# MCU025B_AltRouting_Misc.net
KiCad netlist of a schematic drawn in Altium Designer
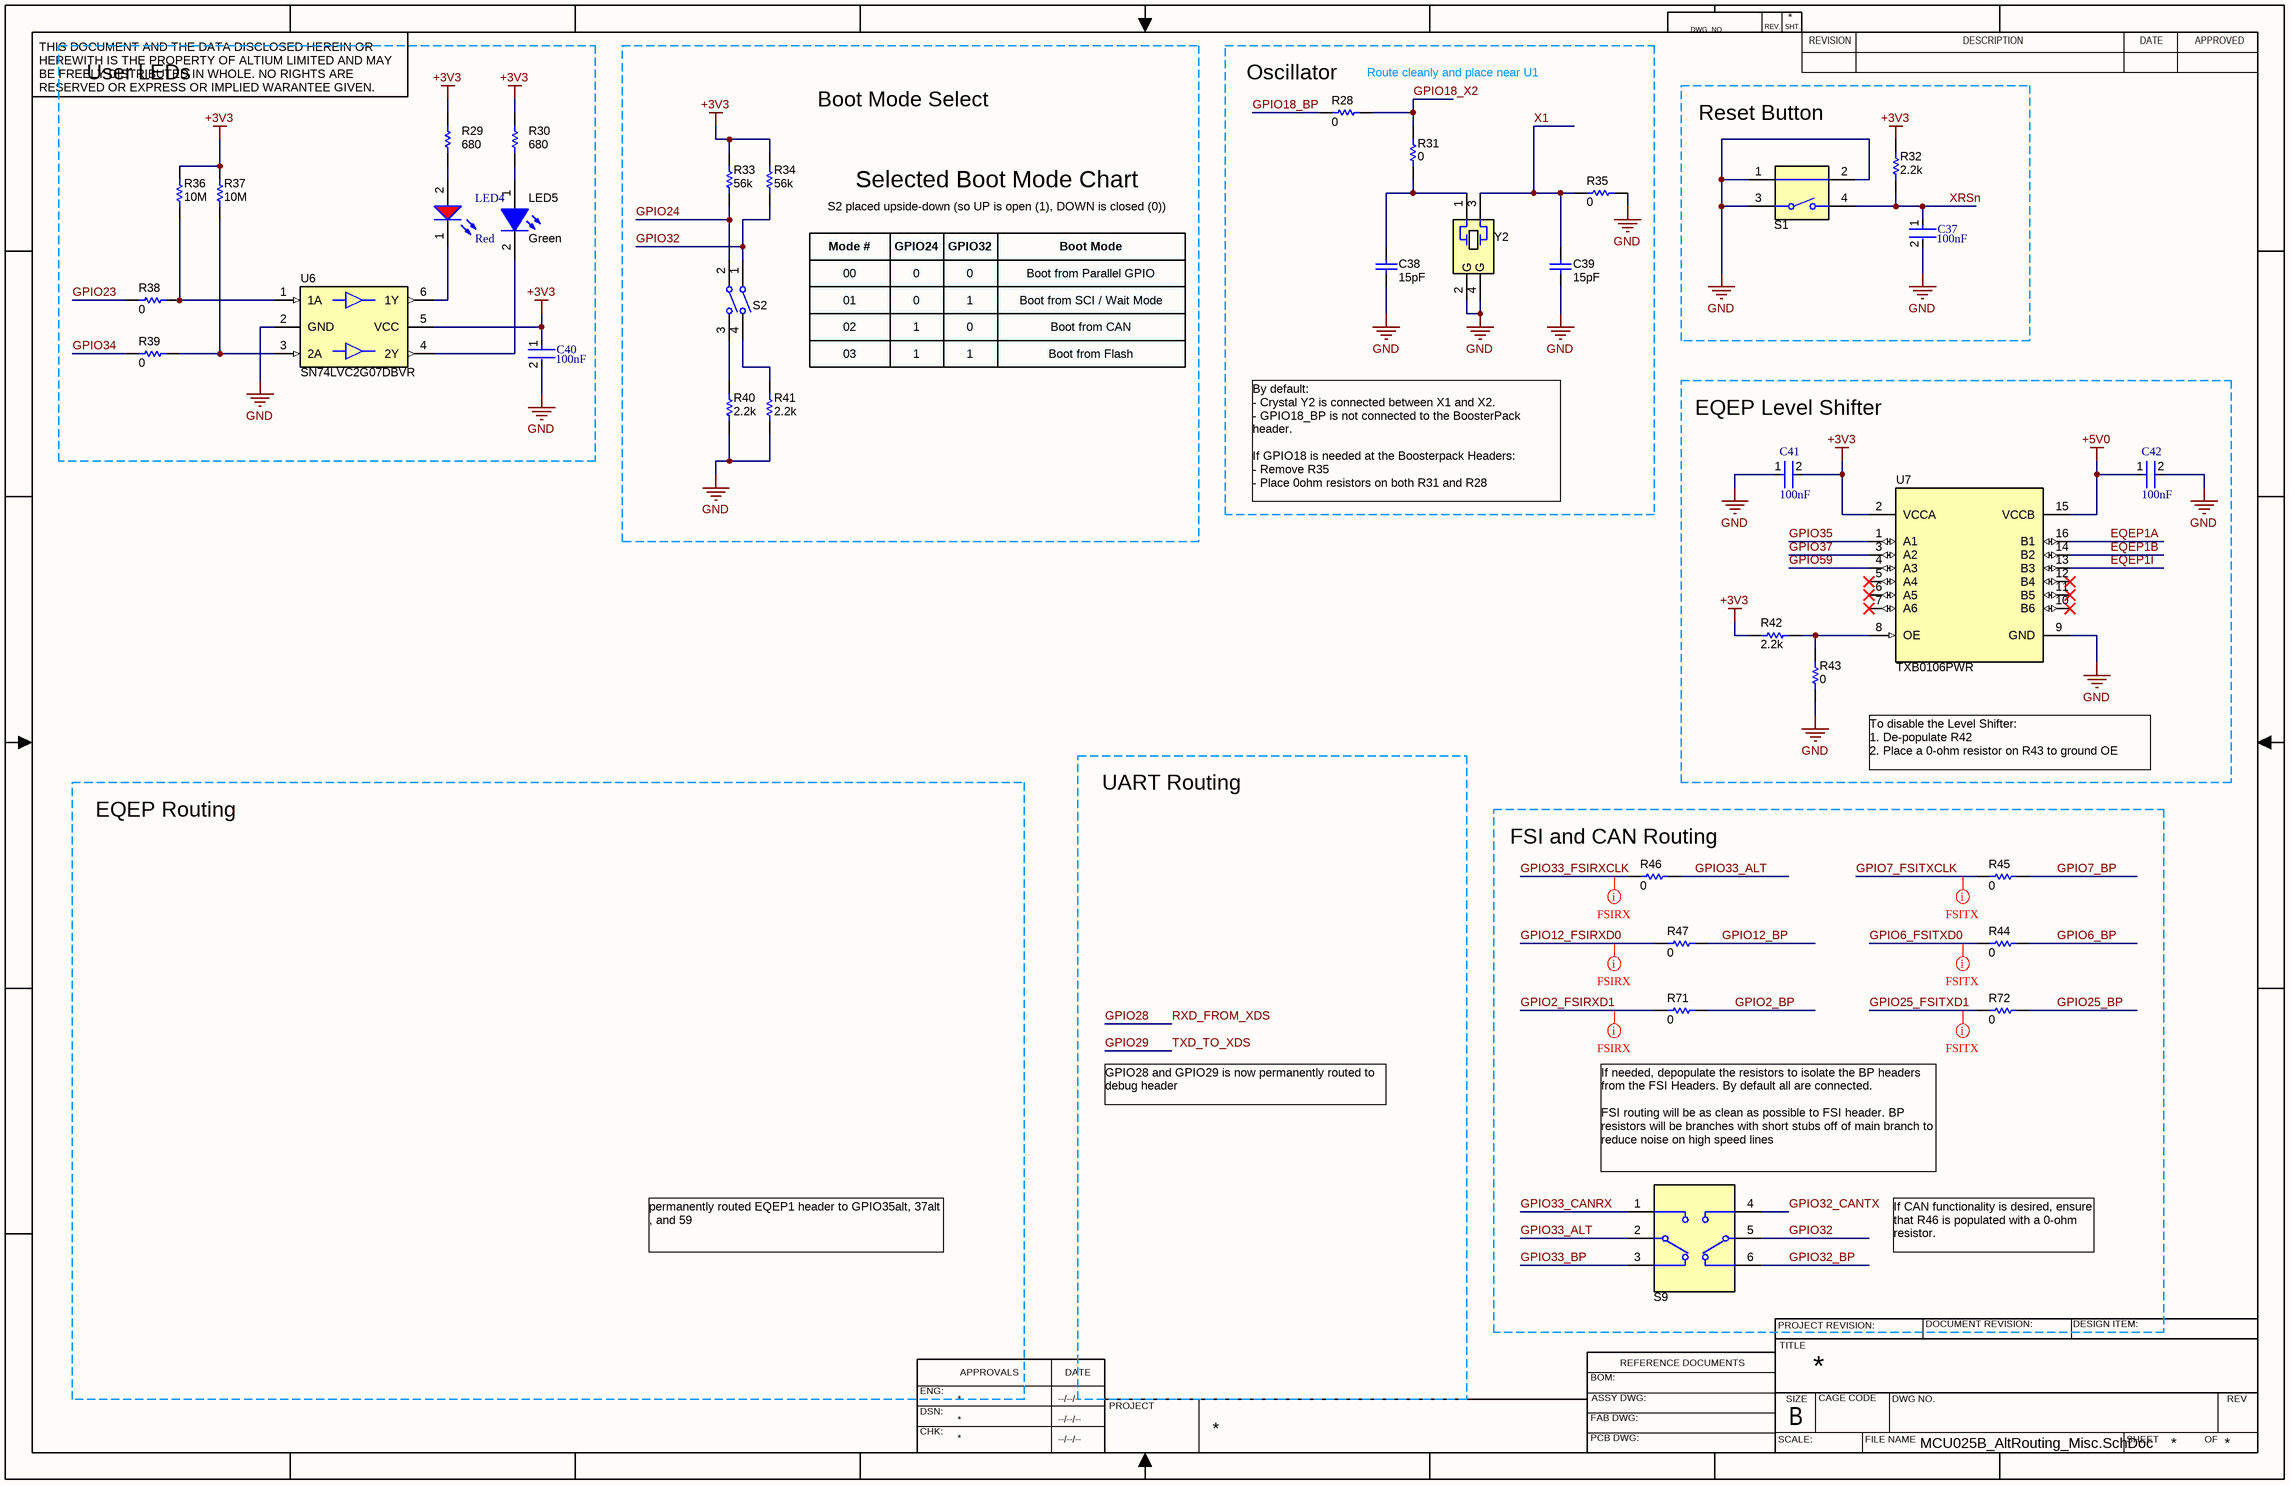
[diagram p0: MCU025B_AltRouting_Misc.SchDoc]

(export (version "E")
  (design (tool "Eeschema 10.0.6"))
  (components
    (comp (ref "C37")
      (value "CL10B104KA8NFNC")
      (footprint "FP-CL10-IPC_C")
      (description "Cap Ceramic 100nF 25V X7R ±10% Pad SMD 0603 +125°C T/R")
      (fields (field (name "TOLERANCE") "10%") (field (name "CAPACITANCE") "100nF"))
      (libsource (lib "Altium Content Vault") (part "b4654b650e69147ec39a6b967a45e02"))
    )
    (comp (ref "C38")
      (value "GRM1555C1H150JA01D")
      (footprint "0402")
      (description "CAP, CERM, 15 pF, 50 V, +/- 5%, C0G/NP0, 0402")
      (fields
        (field (name "VALUEDISPLAYED") "15pF")
        (field (name "MANUFACTURER") "MuRata")
        (field (name "PUBLISHER") "Texas Instruments")
      )
      (libsource (lib "Altium Vault - TI") (part "Capacitor"))
    )
    (comp (ref "C39")
      (value "GRM1555C1H150JA01D")
      (footprint "0402")
      (description "CAP, CERM, 15 pF, 50 V, +/- 5%, C0G/NP0, 0402")
      (fields
        (field (name "VALUEDISPLAYED") "15pF")
        (field (name "MANUFACTURER") "MuRata")
        (field (name "PUBLISHER") "Texas Instruments")
      )
      (libsource (lib "Altium Vault - TI") (part "Capacitor"))
    )
    (comp (ref "C40")
      (value "CL10B104KA8NFNC")
      (footprint "FP-CL10-IPC_C")
      (description "Cap Ceramic 100nF 25V X7R ±10% Pad SMD 0603 +125°C T/R")
      (fields (field (name "TOLERANCE") "10%") (field (name "CAPACITANCE") "100nF"))
      (libsource (lib "Altium Content Vault") (part "b4654b650e69147ec39a6b967a45e02"))
    )
    (comp (ref "C41")
      (value "CL10B104KA8NFNC")
      (footprint "FP-CL10-IPC_C")
      (description "Cap Ceramic 100nF 25V X7R ±10% Pad SMD 0603 +125°C T/R")
      (fields (field (name "TOLERANCE") "10%") (field (name "CAPACITANCE") "100nF"))
      (libsource (lib "Altium Content Vault") (part "b4654b650e69147ec39a6b967a45e02"))
    )
    (comp (ref "C42")
      (value "CL10B104KA8NFNC")
      (footprint "FP-CL10-IPC_C")
      (description "Cap Ceramic 100nF 25V X7R ±10% Pad SMD 0603 +125°C T/R")
      (fields (field (name "TOLERANCE") "10%") (field (name "CAPACITANCE") "100nF"))
      (libsource (lib "Altium Content Vault") (part "b4654b650e69147ec39a6b967a45e02"))
    )
    (comp (ref "LED4")
      (value "150080SS75000")
      (footprint "WL-SMCW_0805_150080xx75000")
      (description "Led, Red, 630 Nm, 1.9 V, 30 Ma, 60 Mcd Rohs Compliant: Yes")
      (fields (field (name "COLOR") "Red"))
      (libsource (lib "Altium Content Vault") (part "LED_Red_2A-1K"))
    )
    (comp (ref "LED5")
      (value "Green")
      (footprint "LED_LTST-C171")
      (description "LED, Green, SMD")
      (fields
        (field (name "MANUFACTURER") "Lite-On")
        (field (name "PARTNUMBER") "LTST-C171GKT")
        (field (name "PUBLISHER") "Texas Instruments")
      )
      (libsource (lib "Altium Vault - TI") (part "LED"))
    )
    (comp (ref "R28")
      (value "CRCW06030000Z0EA")
      (footprint "0603")
      (description "RES, 0, 5%, 0.1 W, AEC-Q200 Grade 0, 0603")
      (fields (field (name "VALUEDISPLAYED") "0") (field (name "MANUFACTURER") "Vishay-Dale"))
      (libsource (lib "Altium Vault - TI") (part "Resistor"))
    )
    (comp (ref "R29")
      (value "CRCW0402680RJNED")
      (footprint "0402")
      (description "RES, 680, 5%, 0.063 W, AEC-Q200 Grade 0, 0402")
      (fields (field (name "MANUFACTURER") "Vishay-Dale") (field (name "VALUEDISPLAYED") "680"))
      (libsource (lib "Altium Vault - TI") (part "CMP-0026962-3"))
    )
    (comp (ref "R30")
      (value "CRCW0402680RJNED")
      (footprint "0402")
      (description "RES, 680, 5%, 0.063 W, AEC-Q200 Grade 0, 0402")
      (fields (field (name "MANUFACTURER") "Vishay-Dale") (field (name "VALUEDISPLAYED") "680"))
      (libsource (lib "Altium Vault - TI") (part "CMP-0026962-3"))
    )
    (comp (ref "R31")
      (value "CRCW06030000Z0EA")
      (footprint "0603")
      (description "RES, 0, 5%, 0.1 W, AEC-Q200 Grade 0, 0603")
      (fields (field (name "VALUEDISPLAYED") "0") (field (name "MANUFACTURER") "Vishay-Dale"))
      (libsource (lib "Altium Vault - TI") (part "Resistor"))
    )
    (comp (ref "R32")
      (value "CRCW04022K20JNED")
      (footprint "0402")
      (description "RES, 2.2 k, 5%, 0.063 W, AEC-Q200 Grade 0, 0402")
      (fields (field (name "VALUEDISPLAYED") "2.2k") (field (name "MANUFACTURER") "Vishay-Dale"))
      (libsource (lib "Altium Vault - TI") (part "Resistor"))
    )
    (comp (ref "R33")
      (value "CRCW040256K0JNED")
      (footprint "0402")
      (description "RES, 56 k, 5%, 0.063 W, AEC-Q200 Grade 0, 0402")
      (fields (field (name "VALUEDISPLAYED") "56k") (field (name "MANUFACTURER") "Vishay-Dale"))
      (libsource (lib "Altium Vault - TI") (part "Resistor"))
    )
    (comp (ref "R34")
      (value "CRCW040256K0JNED")
      (footprint "0402")
      (description "RES, 56 k, 5%, 0.063 W, AEC-Q200 Grade 0, 0402")
      (fields (field (name "VALUEDISPLAYED") "56k") (field (name "MANUFACTURER") "Vishay-Dale"))
      (libsource (lib "Altium Vault - TI") (part "Resistor"))
    )
    (comp (ref "R35")
      (value "CRCW06030000Z0EA")
      (footprint "0603")
      (description "RES, 0, 5%, 0.1 W, AEC-Q200 Grade 0, 0603")
      (fields (field (name "VALUEDISPLAYED") "0") (field (name "MANUFACTURER") "Vishay-Dale"))
      (libsource (lib "Altium Vault - TI") (part "Resistor"))
    )
    (comp (ref "R36")
      (value "CRCW040210M0JNED")
      (footprint "0402")
      (description "RES, 10 M, 5%, 0.063 W, AEC-Q200 Grade 0, 0402")
      (fields (field (name "VALUEDISPLAYED") "10M") (field (name "MANUFACTURER") "Vishay-Dale"))
      (libsource (lib "Altium Vault - TI") (part "Resistor"))
    )
    (comp (ref "R37")
      (value "CRCW040210M0JNED")
      (footprint "0402")
      (description "RES, 10 M, 5%, 0.063 W, AEC-Q200 Grade 0, 0402")
      (fields (field (name "VALUEDISPLAYED") "10M") (field (name "MANUFACTURER") "Vishay-Dale"))
      (libsource (lib "Altium Vault - TI") (part "Resistor"))
    )
    (comp (ref "R38")
      (value "CRCW06030000Z0EA")
      (footprint "0603")
      (description "RES, 0, 5%, 0.1 W, AEC-Q200 Grade 0, 0603")
      (fields (field (name "VALUEDISPLAYED") "0") (field (name "MANUFACTURER") "Vishay-Dale"))
      (libsource (lib "Altium Vault - TI") (part "Resistor"))
    )
    (comp (ref "R39")
      (value "CRCW06030000Z0EA")
      (footprint "0603")
      (description "RES, 0, 5%, 0.1 W, AEC-Q200 Grade 0, 0603")
      (fields (field (name "VALUEDISPLAYED") "0") (field (name "MANUFACTURER") "Vishay-Dale"))
      (libsource (lib "Altium Vault - TI") (part "Resistor"))
    )
    (comp (ref "R40")
      (value "CRCW04022K20JNED")
      (footprint "0402")
      (description "RES, 2.2 k, 5%, 0.063 W, AEC-Q200 Grade 0, 0402")
      (fields (field (name "VALUEDISPLAYED") "2.2k") (field (name "MANUFACTURER") "Vishay-Dale"))
      (libsource (lib "Altium Vault - TI") (part "Resistor"))
    )
    (comp (ref "R41")
      (value "CRCW04022K20JNED")
      (footprint "0402")
      (description "RES, 2.2 k, 5%, 0.063 W, AEC-Q200 Grade 0, 0402")
      (fields (field (name "VALUEDISPLAYED") "2.2k") (field (name "MANUFACTURER") "Vishay-Dale"))
      (libsource (lib "Altium Vault - TI") (part "Resistor"))
    )
    (comp (ref "R42")
      (value "CRCW06032K20JNEA")
      (footprint "0603")
      (description "RES, 2.2 k, 5%, 0.1 W, AEC-Q200 Grade 0, 0603")
      (fields (field (name "VALUEDISPLAYED") "2.2k") (field (name "MANUFACTURER") "Vishay-Dale"))
      (libsource (lib "Altium Vault - TI") (part "Resistor"))
    )
    (comp (ref "R43")
      (value "CRCW06030000Z0EA")
      (footprint "0603")
      (description "RES, 0, 5%, 0.1 W, AEC-Q200 Grade 0, 0603")
      (fields (field (name "VALUEDISPLAYED") "0") (field (name "MANUFACTURER") "Vishay-Dale"))
      (libsource (lib "Altium Vault - TI") (part "Resistor"))
    )
    (comp (ref "R44")
      (value "CRCW06030000Z0EA")
      (footprint "0603")
      (description "RES, 0, 5%, 0.1 W, AEC-Q200 Grade 0, 0603")
      (fields (field (name "VALUEDISPLAYED") "0") (field (name "MANUFACTURER") "Vishay-Dale"))
      (libsource (lib "Altium Vault - TI") (part "Resistor"))
    )
    (comp (ref "R45")
      (value "CRCW06030000Z0EA")
      (footprint "0603")
      (description "RES, 0, 5%, 0.1 W, AEC-Q200 Grade 0, 0603")
      (fields (field (name "VALUEDISPLAYED") "0") (field (name "MANUFACTURER") "Vishay-Dale"))
      (libsource (lib "Altium Vault - TI") (part "Resistor"))
    )
    (comp (ref "R46")
      (value "CRCW06030000Z0EA")
      (footprint "0603")
      (description "RES, 0, 5%, 0.1 W, AEC-Q200 Grade 0, 0603")
      (fields (field (name "VALUEDISPLAYED") "0") (field (name "MANUFACTURER") "Vishay-Dale"))
      (libsource (lib "Altium Vault - TI") (part "Resistor"))
    )
    (comp (ref "R47")
      (value "CRCW06030000Z0EA")
      (footprint "0603")
      (description "RES, 0, 5%, 0.1 W, AEC-Q200 Grade 0, 0603")
      (fields (field (name "VALUEDISPLAYED") "0") (field (name "MANUFACTURER") "Vishay-Dale"))
      (libsource (lib "Altium Vault - TI") (part "Resistor"))
    )
    (comp (ref "R71")
      (value "CRCW06030000Z0EA")
      (footprint "0603")
      (description "RES, 0, 5%, 0.1 W, AEC-Q200 Grade 0, 0603")
      (fields (field (name "VALUEDISPLAYED") "0") (field (name "MANUFACTURER") "Vishay-Dale"))
      (libsource (lib "Altium Vault - TI") (part "Resistor"))
    )
    (comp (ref "R72")
      (value "CRCW06030000Z0EA")
      (footprint "0603")
      (description "RES, 0, 5%, 0.1 W, AEC-Q200 Grade 0, 0603")
      (fields (field (name "VALUEDISPLAYED") "0") (field (name "MANUFACTURER") "Vishay-Dale"))
      (libsource (lib "Altium Vault - TI") (part "Resistor"))
    )
    (comp (ref "S1")
      (value "1188E-1K2-V-TR")
      (footprint "SW_1188E")
      (description "Switch, SPST, 0.05 A, 12 VDC, SMD")
      (fields (field (name "MANUFACTURER") "Diptronics") (field (name "PUBLISHER") "Texas Instruments"))
      (libsource (lib "Altium Vault - TI") (part "SW_1188E"))
    )
    (comp (ref "S2")
      (value "218-2LPST")
      (footprint "SW_218-2LP")
      (description "Switch, SPST, 2 Pos, 25mA, 24VDC, SMD")
      (fields
        (field (name "MANUFACTURER") "CTS Electrocomponents")
        (field (name "PUBLISHER") "Texas Instruments")
      )
      (libsource (lib "Altium Vault - TI") (part "SW_2SPST"))
    )
    (comp (ref "S9")
      (value "CAS-220TA")
      (footprint "SW_CAS-220TA")
      (description "SLIDE SWITCH DPDT  .1A, SMT")
      (fields
        (field (name "MANUFACTURER") "Copal Electronics")
        (field (name "PUBLISHER") "Texas Instruments")
      )
      (libsource (lib "Altium Vault - TI") (part "SW_CAS-220TA"))
    )
    (comp (ref "U6")
      (value "SN74LVC2G07DBVR")
      (footprint "DBV0006A_N")
      (description "Dual Buffer/Driver with Open-Drain Output, DBV0006A, LARGE T&R")
      (fields
        (field (name "GENERIC PART NUMBER") "SN74LVC2G07")
        (field (name "MANUFACTURER") "Texas Instruments")
      )
      (libsource (lib "Altium Vault - TI") (part "CMP-0051789-2"))
    )
    (comp (ref "U7")
      (value "TXB0106PWR")
      (footprint "PW0016A_N")
      (fields
        (field (name "MANUFACTURER") "Texas Instruments")
        (field (name "PUBLISHER") "Texas Instruments")
      )
      (libsource (lib "Altium Vault - TI") (part "TXB0106PW"))
    )
    (comp (ref "Y2")
      (value "ECS-200-18-30B-AGN-TR")
      (footprint "ECS_ECX-53B")
      (description "Crystal, 20 MHz, 25 ppm, 18, SMD")
      (fields (field (name "MANUFACTURER") "ECS Inc."))
      (libsource (lib "Altium Vault - TI") (part "CMP-0080365-1"))
    )
  )
  (nets
    (net (code "1") (name "+3V3") (class "Default")
      (node (ref "C40") (pin "1") (pinfunction "1_1") (pintype "passive"))
      (node (ref "C41") (pin "2") (pinfunction "2_2") (pintype "passive"))
      (node (ref "R29") (pin "2") (pinfunction "2_2") (pintype "passive"))
      (node (ref "R30") (pin "2") (pinfunction "2_2") (pintype "passive"))
      (node (ref "R32") (pin "2") (pinfunction "2_2") (pintype "passive"))
      (node (ref "R33") (pin "2") (pinfunction "2_2") (pintype "passive"))
      (node (ref "R34") (pin "2") (pinfunction "2_2") (pintype "passive"))
      (node (ref "R36") (pin "2") (pinfunction "2_2") (pintype "passive"))
      (node (ref "R37") (pin "2") (pinfunction "2_2") (pintype "passive"))
      (node (ref "R42") (pin "1") (pinfunction "1_1") (pintype "passive"))
      (node (ref "U6") (pin "5") (pinfunction "VCC_5") (pintype "power_in"))
      (node (ref "U7") (pin "2") (pinfunction "VCCA_2") (pintype "power_in"))
    )
    (net (code "2") (name "+5V0") (class "Default")
      (node (ref "C42") (pin "1") (pinfunction "1_1") (pintype "passive"))
      (node (ref "U7") (pin "15") (pinfunction "VCCB_15") (pintype "power_in"))
    )
    (net (code "3") (name "/EQEP1A") (class "Default")
      (node (ref "U7") (pin "16") (pinfunction "B1_16") (pintype "bidirectional"))
    )
    (net (code "4") (name "/EQEP1B") (class "Default")
      (node (ref "U7") (pin "14") (pinfunction "B2_14") (pintype "bidirectional"))
    )
    (net (code "5") (name "/EQEP1I") (class "Default")
      (node (ref "U7") (pin "13") (pinfunction "B3_13") (pintype "bidirectional"))
    )
    (net (code "6") (name "/GPIO2_BP") (class "Default")
      (node (ref "R71") (pin "2") (pinfunction "2_2") (pintype "passive"))
    )
    (net (code "7") (name "/GPIO2_FSIRXD1") (class "Default")
      (node (ref "R71") (pin "1") (pinfunction "1_1") (pintype "passive"))
    )
    (net (code "8") (name "/GPIO6_BP") (class "Default")
      (node (ref "R44") (pin "2") (pinfunction "2_2") (pintype "passive"))
    )
    (net (code "9") (name "/GPIO6_FSITXD0") (class "Default")
      (node (ref "R44") (pin "1") (pinfunction "1_1") (pintype "passive"))
    )
    (net (code "10") (name "/GPIO7_BP") (class "Default")
      (node (ref "R45") (pin "2") (pinfunction "2_2") (pintype "passive"))
    )
    (net (code "11") (name "/GPIO7_FSITXCLK") (class "Default")
      (node (ref "R45") (pin "1") (pinfunction "1_1") (pintype "passive"))
    )
    (net (code "12") (name "/GPIO12_BP") (class "Default")
      (node (ref "R47") (pin "2") (pinfunction "2_2") (pintype "passive"))
    )
    (net (code "13") (name "/GPIO12_FSIRXD0") (class "Default")
      (node (ref "R47") (pin "1") (pinfunction "1_1") (pintype "passive"))
    )
    (net (code "14") (name "/GPIO18_BP") (class "Default")
      (node (ref "R28") (pin "1") (pinfunction "1_1") (pintype "passive"))
    )
    (net (code "15") (name "/GPIO18_X2") (class "Default")
      (node (ref "R28") (pin "2") (pinfunction "2_2") (pintype "passive"))
      (node (ref "R31") (pin "2") (pinfunction "2_2") (pintype "passive"))
    )
    (net (code "16") (name "/GPIO23") (class "Default")
      (node (ref "R38") (pin "1") (pinfunction "1_1") (pintype "passive"))
    )
    (net (code "17") (name "/GPIO24") (class "Default")
      (node (ref "R33") (pin "1") (pinfunction "1_1") (pintype "passive"))
      (node (ref "S2") (pin "2") (pinfunction "2_2") (pintype "passive"))
    )
    (net (code "18") (name "/GPIO25_BP") (class "Default")
      (node (ref "R72") (pin "2") (pinfunction "2_2") (pintype "passive"))
    )
    (net (code "19") (name "/GPIO25_FSITXD1") (class "Default")
      (node (ref "R72") (pin "1") (pinfunction "1_1") (pintype "passive"))
    )
    (net (code "22") (name "/GPIO32") (class "Default")
      (node (ref "R34") (pin "1") (pinfunction "1_1") (pintype "passive"))
      (node (ref "S2") (pin "1") (pinfunction "1_1") (pintype "passive"))
      (node (ref "S9") (pin "5") (pinfunction "5_5") (pintype "passive"))
    )
    (net (code "23") (name "/GPIO32_BP") (class "Default")
      (node (ref "S9") (pin "6") (pinfunction "6_6") (pintype "passive"))
    )
    (net (code "24") (name "/GPIO32_CANTX") (class "Default")
      (node (ref "S9") (pin "4") (pinfunction "4_4") (pintype "passive"))
    )
    (net (code "25") (name "/GPIO33_ALT") (class "Default")
      (node (ref "R46") (pin "2") (pinfunction "2_2") (pintype "passive"))
      (node (ref "S9") (pin "2") (pinfunction "2_2") (pintype "passive"))
    )
    (net (code "26") (name "/GPIO33_BP") (class "Default")
      (node (ref "S9") (pin "3") (pinfunction "3_3") (pintype "passive"))
    )
    (net (code "27") (name "/GPIO33_CANRX") (class "Default")
      (node (ref "S9") (pin "1") (pinfunction "1_1") (pintype "passive"))
    )
    (net (code "28") (name "/GPIO33_FSIRXCLK") (class "Default")
      (node (ref "R46") (pin "1") (pinfunction "1_1") (pintype "passive"))
    )
    (net (code "29") (name "/GPIO34") (class "Default")
      (node (ref "R39") (pin "1") (pinfunction "1_1") (pintype "passive"))
    )
    (net (code "30") (name "/GPIO35") (class "Default")
      (node (ref "U7") (pin "1") (pinfunction "A1_1") (pintype "bidirectional"))
    )
    (net (code "31") (name "/GPIO37") (class "Default")
      (node (ref "U7") (pin "3") (pinfunction "A2_3") (pintype "bidirectional"))
    )
    (net (code "32") (name "/GPIO59") (class "Default")
      (node (ref "U7") (pin "4") (pinfunction "A3_4") (pintype "bidirectional"))
    )
    (net (code "33") (name "/X1") (class "Default")
      (node (ref "C39") (pin "1") (pinfunction "1_1") (pintype "passive"))
      (node (ref "R35") (pin "1") (pinfunction "1_1") (pintype "passive"))
      (node (ref "Y2") (pin "3") (pinfunction "3_3") (pintype "passive"))
    )
    (net (code "34") (name "/XRSn") (class "Default")
      (node (ref "C37") (pin "1") (pinfunction "1_1") (pintype "passive"))
      (node (ref "R32") (pin "1") (pinfunction "1_1") (pintype "passive"))
      (node (ref "S1") (pin "4") (pinfunction "4_4") (pintype "passive"))
    )
    (net (code "35") (name "GND") (class "Default")
      (node (ref "C37") (pin "2") (pinfunction "2_2") (pintype "passive"))
      (node (ref "C38") (pin "2") (pinfunction "2_2") (pintype "passive"))
      (node (ref "C39") (pin "2") (pinfunction "2_2") (pintype "passive"))
      (node (ref "C40") (pin "2") (pinfunction "2_2") (pintype "passive"))
      (node (ref "C41") (pin "1") (pinfunction "1_1") (pintype "passive"))
      (node (ref "C42") (pin "2") (pinfunction "2_2") (pintype "passive"))
      (node (ref "R35") (pin "2") (pinfunction "2_2") (pintype "passive"))
      (node (ref "R40") (pin "1") (pinfunction "1_1") (pintype "passive"))
      (node (ref "R41") (pin "1") (pinfunction "1_1") (pintype "passive"))
      (node (ref "R43") (pin "1") (pinfunction "1_1") (pintype "passive"))
      (node (ref "S1") (pin "1") (pinfunction "1_1") (pintype "passive"))
      (node (ref "S1") (pin "2") (pinfunction "2_2") (pintype "passive"))
      (node (ref "S1") (pin "3") (pinfunction "3_3") (pintype "passive"))
      (node (ref "U6") (pin "2") (pinfunction "GND_2") (pintype "power_in"))
      (node (ref "U7") (pin "9") (pinfunction "GND_9") (pintype "power_in"))
      (node (ref "Y2") (pin "2") (pinfunction "GND_2") (pintype "power_in"))
      (node (ref "Y2") (pin "4") (pinfunction "GND_4") (pintype "power_in"))
    )
    (net (code "36") (name "Net-(C38-Pad1)") (class "Default")
      (node (ref "C38") (pin "1") (pinfunction "1_1") (pintype "passive"))
      (node (ref "R31") (pin "1") (pinfunction "1_1") (pintype "passive"))
      (node (ref "Y2") (pin "1") (pinfunction "1_1") (pintype "passive"))
    )
    (net (code "37") (name "Net-(LED4-A)") (class "Default")
      (node (ref "LED4") (pin "2") (pinfunction "A_2") (pintype "passive"))
      (node (ref "R29") (pin "1") (pinfunction "1_1") (pintype "passive"))
    )
    (net (code "38") (name "Net-(LED4-K)") (class "Default")
      (node (ref "LED4") (pin "1") (pinfunction "K_1") (pintype "passive"))
      (node (ref "U6") (pin "6") (pinfunction "1Y_6") (pintype "output"))
    )
    (net (code "39") (name "Net-(LED5-A)") (class "Default")
      (node (ref "LED5") (pin "1") (pinfunction "A_1") (pintype "passive"))
      (node (ref "R30") (pin "1") (pinfunction "1_1") (pintype "passive"))
    )
    (net (code "40") (name "Net-(LED5-K)") (class "Default")
      (node (ref "LED5") (pin "2") (pinfunction "K_2") (pintype "passive"))
      (node (ref "U6") (pin "4") (pinfunction "2Y_4") (pintype "output"))
    )
    (net (code "41") (name "Net-(R40-Pad2)") (class "Default")
      (node (ref "R40") (pin "2") (pinfunction "2_2") (pintype "passive"))
      (node (ref "S2") (pin "3") (pinfunction "3_3") (pintype "passive"))
    )
    (net (code "42") (name "Net-(R41-Pad2)") (class "Default")
      (node (ref "R41") (pin "2") (pinfunction "2_2") (pintype "passive"))
      (node (ref "S2") (pin "4") (pinfunction "4_4") (pintype "passive"))
    )
    (net (code "43") (name "Net-(U6-1A)") (class "Default")
      (node (ref "R36") (pin "1") (pinfunction "1_1") (pintype "passive"))
      (node (ref "R38") (pin "2") (pinfunction "2_2") (pintype "passive"))
      (node (ref "U6") (pin "1") (pinfunction "1A_1") (pintype "input"))
    )
    (net (code "44") (name "Net-(U6-2A)") (class "Default")
      (node (ref "R37") (pin "1") (pinfunction "1_1") (pintype "passive"))
      (node (ref "R39") (pin "2") (pinfunction "2_2") (pintype "passive"))
      (node (ref "U6") (pin "3") (pinfunction "2A_3") (pintype "input"))
    )
    (net (code "45") (name "Net-(U7-OE)") (class "Default")
      (node (ref "R42") (pin "2") (pinfunction "2_2") (pintype "passive"))
      (node (ref "R43") (pin "2") (pinfunction "2_2") (pintype "passive"))
      (node (ref "U7") (pin "8") (pinfunction "OE_8") (pintype "input"))
    )
    (net (code "46") (name "unconnected-(U7-A4-Pad5)") (class "Default")
      (node (ref "U7") (pin "5") (pinfunction "A4_5") (pintype "bidirectional+no_connect"))
    )
    (net (code "47") (name "unconnected-(U7-A5-Pad6)") (class "Default")
      (node (ref "U7") (pin "6") (pinfunction "A5_6") (pintype "bidirectional+no_connect"))
    )
    (net (code "48") (name "unconnected-(U7-A6-Pad7)") (class "Default")
      (node (ref "U7") (pin "7") (pinfunction "A6_7") (pintype "bidirectional+no_connect"))
    )
    (net (code "49") (name "unconnected-(U7-B4-Pad12)") (class "Default")
      (node (ref "U7") (pin "12") (pinfunction "B4_12") (pintype "bidirectional+no_connect"))
    )
    (net (code "50") (name "unconnected-(U7-B5-Pad11)") (class "Default")
      (node (ref "U7") (pin "11") (pinfunction "B5_11") (pintype "bidirectional+no_connect"))
    )
    (net (code "51") (name "unconnected-(U7-B6-Pad10)") (class "Default")
      (node (ref "U7") (pin "10") (pinfunction "B6_10") (pintype "bidirectional+no_connect"))
    )
  )
)
